# USB.net
KiCad netlist of a schematic drawn in Altium Designer
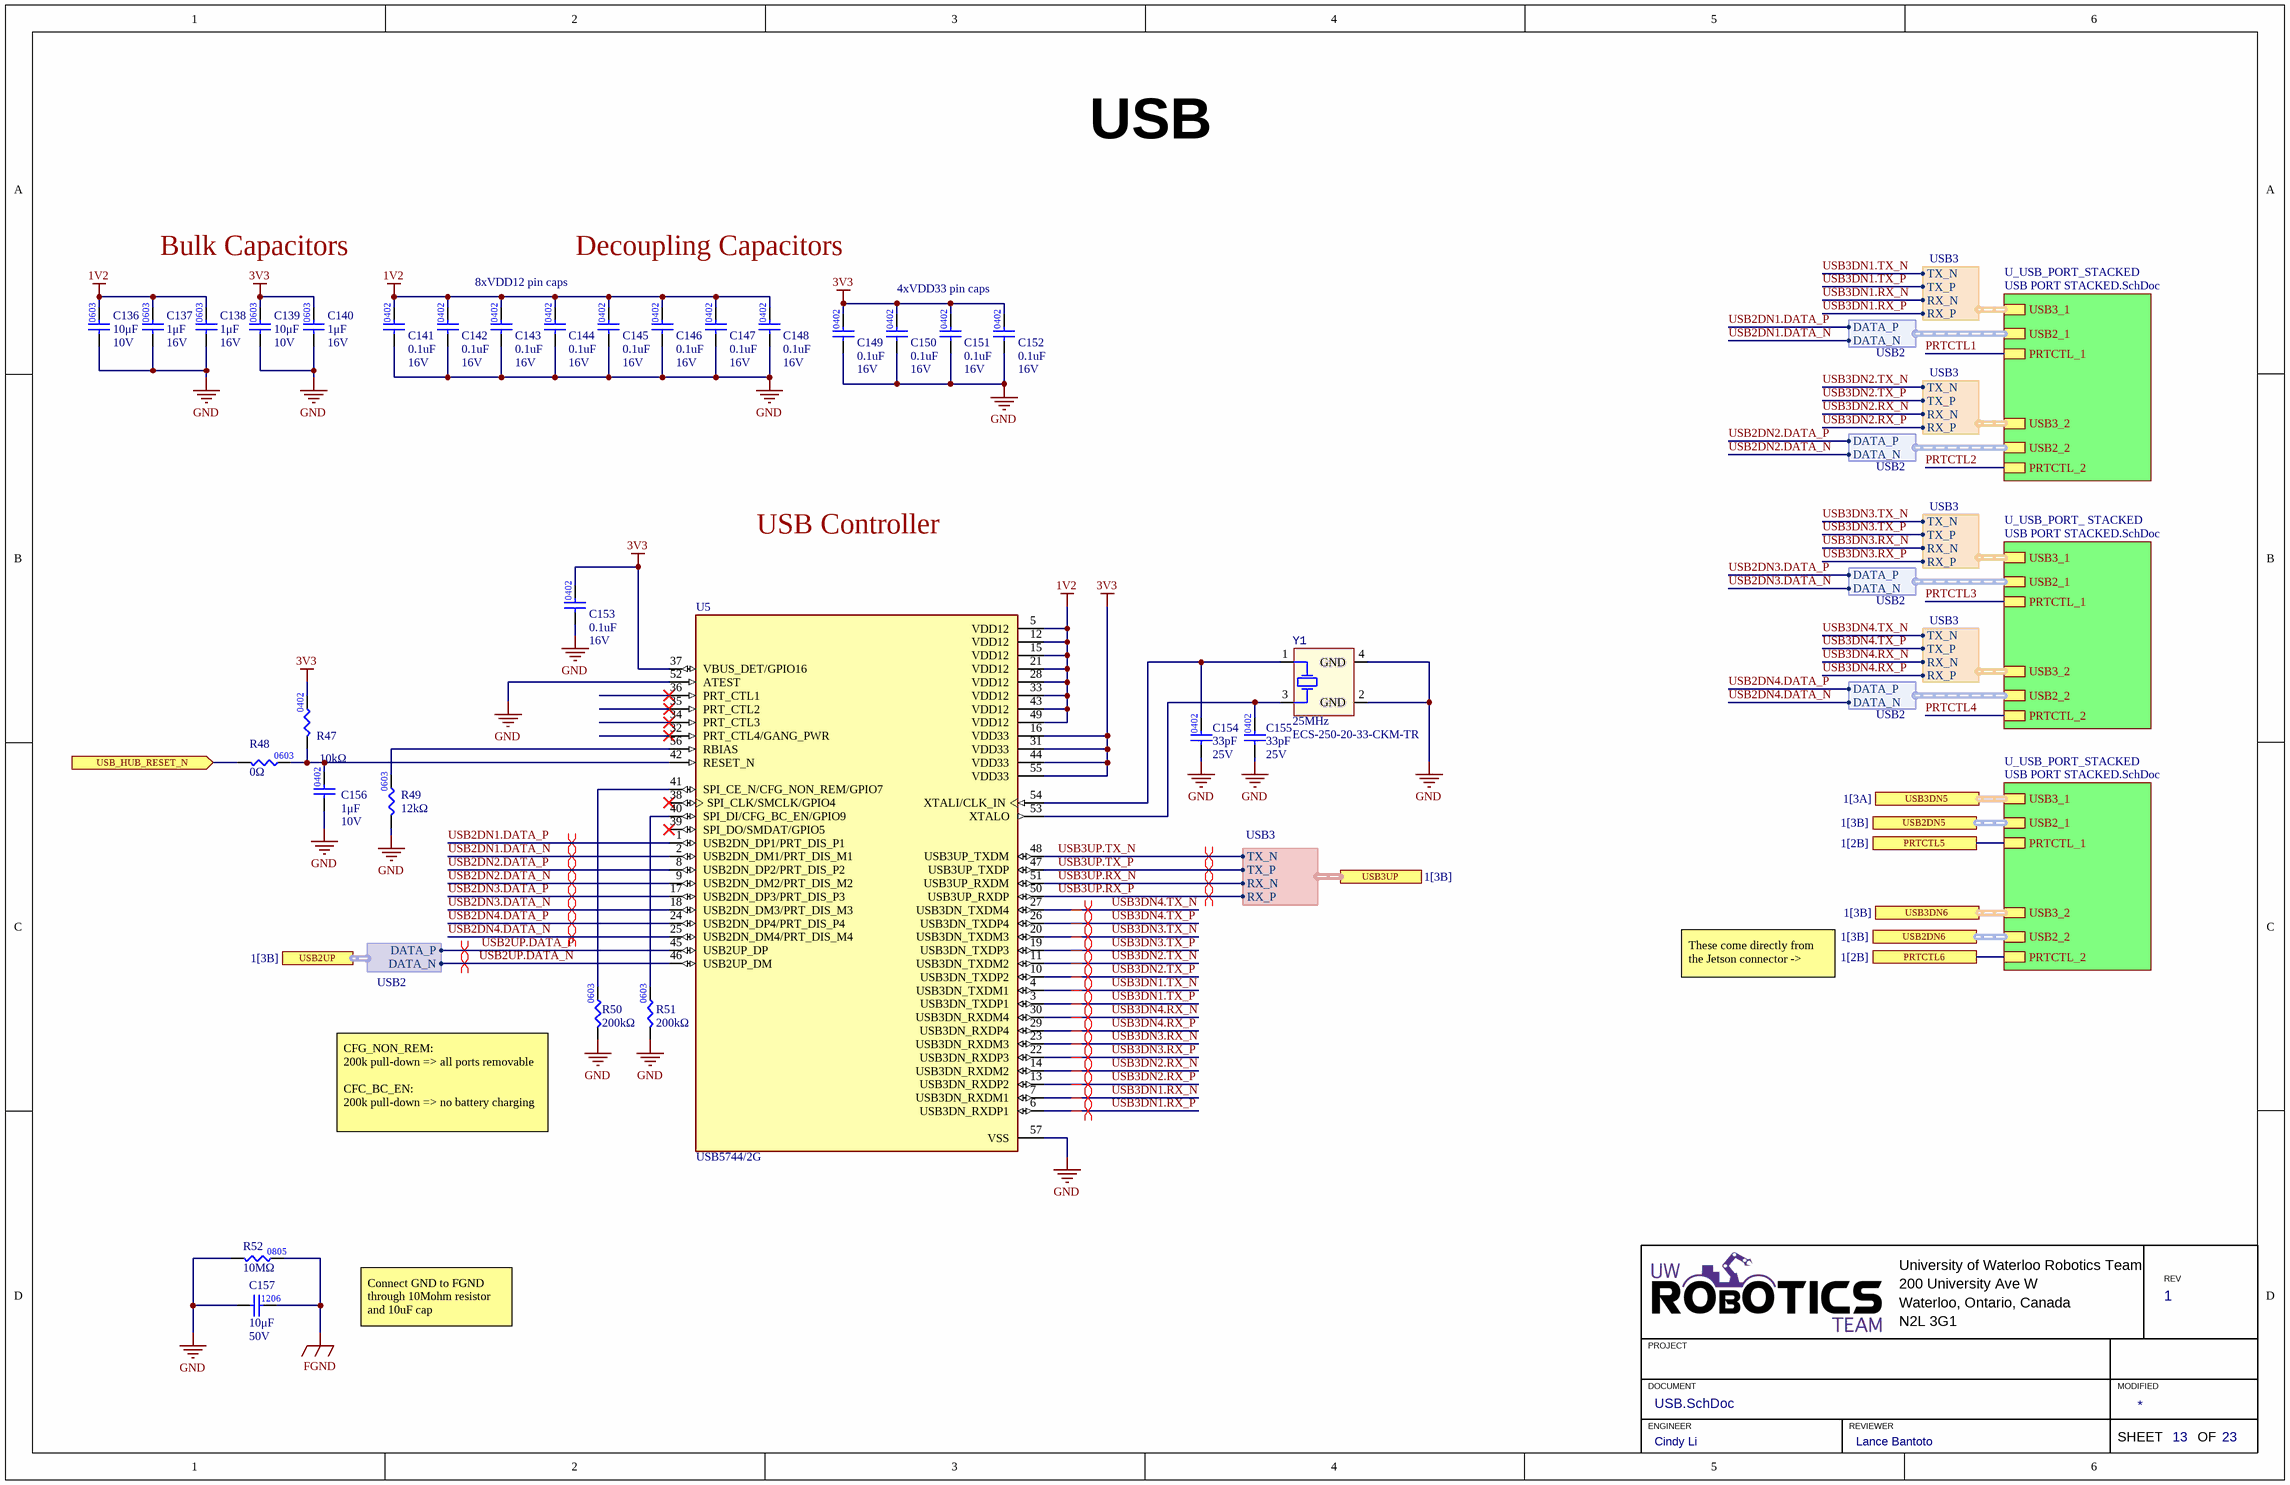
[diagram p0: USB.SchDoc]

(export (version "E")
  (design (tool "Eeschema 10.0.6"))
  (components
    (comp (ref "C136")
      (value "10μF")
      (footprint "CAP0603")
      (description "CAP CER 10UF 10V X5R 0603")
      (fields (field (name "VOLTAGE RATING") "10V") (field (name "Comment") "CAP_10uF_10V_0603"))
      (libsource (lib "UWRT_Schematic_Library_2020") (part "CAP_10uF_10V_0603"))
    )
    (comp (ref "C137")
      (value "1μF")
      (footprint "CAP0603")
      (description "CAP CER 1UF 16V Y5V 0603")
      (fields (field (name "VOLTAGE RATING") "16V") (field (name "Comment") "CAP_1uF_16V_0603"))
      (libsource (lib "UWRT_Schematic_Library_2020") (part "CAP_1uF_16V_0603"))
    )
    (comp (ref "C138")
      (value "1μF")
      (footprint "CAP0603")
      (description "CAP CER 1UF 16V Y5V 0603")
      (fields (field (name "VOLTAGE RATING") "16V") (field (name "Comment") "CAP_1uF_16V_0603"))
      (libsource (lib "UWRT_Schematic_Library_2020") (part "CAP_1uF_16V_0603"))
    )
    (comp (ref "C139")
      (value "10μF")
      (footprint "CAP0603")
      (description "CAP CER 10UF 10V X5R 0603")
      (fields (field (name "VOLTAGE RATING") "10V") (field (name "Comment") "CAP_10uF_10V_0603"))
      (libsource (lib "UWRT_Schematic_Library_2020") (part "CAP_10uF_10V_0603"))
    )
    (comp (ref "C140")
      (value "1μF")
      (footprint "CAP0603")
      (description "CAP CER 1UF 16V Y5V 0603")
      (fields (field (name "VOLTAGE RATING") "16V") (field (name "Comment") "CAP_1uF_16V_0603"))
      (libsource (lib "UWRT_Schematic_Library_2020") (part "CAP_1uF_16V_0603"))
    )
    (comp (ref "C141")
      (value "CAP_0.1uF_16V_X7R_0402")
      (footprint "CAP0402")
      (description "Ceramic Capacitor, Ceramic")
      (fields
        (field (name "MANUFACTURER") "Taiyo Yuden")
        (field (name "MANUFACTURER PART NUMBER") "LMK212AC6106MD-T")
        (field (name "RATED DC VOLTAGE (URDC)") "16V")
        (field (name "CAPACITANCE") "0.1uF")
      )
      (libsource (lib "UWRT_Schematic_Library_2020") (part "CAP_0.1uF_16V_X7R_0402"))
    )
    (comp (ref "C142")
      (value "CAP_0.1uF_16V_X7R_0402")
      (footprint "CAP0402")
      (description "Ceramic Capacitor, Ceramic")
      (fields
        (field (name "MANUFACTURER") "Taiyo Yuden")
        (field (name "MANUFACTURER PART NUMBER") "LMK212AC6106MD-T")
        (field (name "RATED DC VOLTAGE (URDC)") "16V")
        (field (name "CAPACITANCE") "0.1uF")
      )
      (libsource (lib "UWRT_Schematic_Library_2020") (part "CAP_0.1uF_16V_X7R_0402"))
    )
    (comp (ref "C143")
      (value "CAP_0.1uF_16V_X7R_0402")
      (footprint "CAP0402")
      (description "Ceramic Capacitor, Ceramic")
      (fields
        (field (name "MANUFACTURER") "Taiyo Yuden")
        (field (name "MANUFACTURER PART NUMBER") "LMK212AC6106MD-T")
        (field (name "RATED DC VOLTAGE (URDC)") "16V")
        (field (name "CAPACITANCE") "0.1uF")
      )
      (libsource (lib "UWRT_Schematic_Library_2020") (part "CAP_0.1uF_16V_X7R_0402"))
    )
    (comp (ref "C144")
      (value "CAP_0.1uF_16V_X7R_0402")
      (footprint "CAP0402")
      (description "Ceramic Capacitor, Ceramic")
      (fields
        (field (name "MANUFACTURER") "Taiyo Yuden")
        (field (name "MANUFACTURER PART NUMBER") "LMK212AC6106MD-T")
        (field (name "RATED DC VOLTAGE (URDC)") "16V")
        (field (name "CAPACITANCE") "0.1uF")
      )
      (libsource (lib "UWRT_Schematic_Library_2020") (part "CAP_0.1uF_16V_X7R_0402"))
    )
    (comp (ref "C145")
      (value "CAP_0.1uF_16V_X7R_0402")
      (footprint "CAP0402")
      (description "Ceramic Capacitor, Ceramic")
      (fields
        (field (name "MANUFACTURER") "Taiyo Yuden")
        (field (name "MANUFACTURER PART NUMBER") "LMK212AC6106MD-T")
        (field (name "RATED DC VOLTAGE (URDC)") "16V")
        (field (name "CAPACITANCE") "0.1uF")
      )
      (libsource (lib "UWRT_Schematic_Library_2020") (part "CAP_0.1uF_16V_X7R_0402"))
    )
    (comp (ref "C146")
      (value "CAP_0.1uF_16V_X7R_0402")
      (footprint "CAP0402")
      (description "Ceramic Capacitor, Ceramic")
      (fields
        (field (name "MANUFACTURER") "Taiyo Yuden")
        (field (name "MANUFACTURER PART NUMBER") "LMK212AC6106MD-T")
        (field (name "RATED DC VOLTAGE (URDC)") "16V")
        (field (name "CAPACITANCE") "0.1uF")
      )
      (libsource (lib "UWRT_Schematic_Library_2020") (part "CAP_0.1uF_16V_X7R_0402"))
    )
    (comp (ref "C147")
      (value "CAP_0.1uF_16V_X7R_0402")
      (footprint "CAP0402")
      (description "Ceramic Capacitor, Ceramic")
      (fields
        (field (name "MANUFACTURER") "Taiyo Yuden")
        (field (name "MANUFACTURER PART NUMBER") "LMK212AC6106MD-T")
        (field (name "RATED DC VOLTAGE (URDC)") "16V")
        (field (name "CAPACITANCE") "0.1uF")
      )
      (libsource (lib "UWRT_Schematic_Library_2020") (part "CAP_0.1uF_16V_X7R_0402"))
    )
    (comp (ref "C148")
      (value "CAP_0.1uF_16V_X7R_0402")
      (footprint "CAP0402")
      (description "Ceramic Capacitor, Ceramic")
      (fields
        (field (name "MANUFACTURER") "Taiyo Yuden")
        (field (name "MANUFACTURER PART NUMBER") "LMK212AC6106MD-T")
        (field (name "RATED DC VOLTAGE (URDC)") "16V")
        (field (name "CAPACITANCE") "0.1uF")
      )
      (libsource (lib "UWRT_Schematic_Library_2020") (part "CAP_0.1uF_16V_X7R_0402"))
    )
    (comp (ref "C149")
      (value "CAP_0.1uF_16V_X7R_0402")
      (footprint "CAP0402")
      (description "Ceramic Capacitor, Ceramic")
      (fields
        (field (name "MANUFACTURER") "Taiyo Yuden")
        (field (name "MANUFACTURER PART NUMBER") "LMK212AC6106MD-T")
        (field (name "RATED DC VOLTAGE (URDC)") "16V")
        (field (name "CAPACITANCE") "0.1uF")
      )
      (libsource (lib "UWRT_Schematic_Library_2020") (part "CAP_0.1uF_16V_X7R_0402"))
    )
    (comp (ref "C150")
      (value "CAP_0.1uF_16V_X7R_0402")
      (footprint "CAP0402")
      (description "Ceramic Capacitor, Ceramic")
      (fields
        (field (name "MANUFACTURER") "Taiyo Yuden")
        (field (name "MANUFACTURER PART NUMBER") "LMK212AC6106MD-T")
        (field (name "RATED DC VOLTAGE (URDC)") "16V")
        (field (name "CAPACITANCE") "0.1uF")
      )
      (libsource (lib "UWRT_Schematic_Library_2020") (part "CAP_0.1uF_16V_X7R_0402"))
    )
    (comp (ref "C151")
      (value "CAP_0.1uF_16V_X7R_0402")
      (footprint "CAP0402")
      (description "Ceramic Capacitor, Ceramic")
      (fields
        (field (name "MANUFACTURER") "Taiyo Yuden")
        (field (name "MANUFACTURER PART NUMBER") "LMK212AC6106MD-T")
        (field (name "RATED DC VOLTAGE (URDC)") "16V")
        (field (name "CAPACITANCE") "0.1uF")
      )
      (libsource (lib "UWRT_Schematic_Library_2020") (part "CAP_0.1uF_16V_X7R_0402"))
    )
    (comp (ref "C152")
      (value "CAP_0.1uF_16V_X7R_0402")
      (footprint "CAP0402")
      (description "Ceramic Capacitor, Ceramic")
      (fields
        (field (name "MANUFACTURER") "Taiyo Yuden")
        (field (name "MANUFACTURER PART NUMBER") "LMK212AC6106MD-T")
        (field (name "RATED DC VOLTAGE (URDC)") "16V")
        (field (name "CAPACITANCE") "0.1uF")
      )
      (libsource (lib "UWRT_Schematic_Library_2020") (part "CAP_0.1uF_16V_X7R_0402"))
    )
    (comp (ref "C153")
      (value "CAP_0.1uF_16V_X7R_0402")
      (footprint "CAP0402")
      (description "Ceramic Capacitor, Ceramic")
      (fields
        (field (name "MANUFACTURER") "Taiyo Yuden")
        (field (name "MANUFACTURER PART NUMBER") "LMK212AC6106MD-T")
        (field (name "RATED DC VOLTAGE (URDC)") "16V")
        (field (name "CAPACITANCE") "0.1uF")
      )
      (libsource (lib "UWRT_Schematic_Library_2020") (part "CAP_0.1uF_16V_X7R_0402"))
    )
    (comp (ref "C154")
      (value "33pF")
      (footprint "CAP0402")
      (description "CAP CER 33PF 25V C0G/NP0 0402")
      (fields (field (name "VOLTAGE RATING") "25V") (field (name "Comment") "CAP_33pF_25V_0402"))
      (libsource (lib "UWRT_Schematic_Library_2020") (part "CAP_33pF_25V_0402"))
    )
    (comp (ref "C155")
      (value "33pF")
      (footprint "CAP0402")
      (description "CAP CER 33PF 25V C0G/NP0 0402")
      (fields (field (name "VOLTAGE RATING") "25V") (field (name "Comment") "CAP_33pF_25V_0402"))
      (libsource (lib "UWRT_Schematic_Library_2020") (part "CAP_33pF_25V_0402"))
    )
    (comp (ref "C156")
      (value "CAP_1UF_10V_0402_X5R")
      (footprint "CAP0402")
      (description "CAP CER 1UF 10V X5R 0402")
      (fields
        (field (name "MANUFACTURER") "Kyocera AVX")
        (field (name "MANUFACTURER PART NUMBER") "0402ZD105MAT2A")
        (field (name "CAPACITANCE") "1μF")
        (field (name "RATED DC VOLTAGE (URDC)") "10V")
      )
      (libsource (lib "UWRT_Schematic_Library_2020") (part "CAP_1UF_10V_0402_X5R"))
    )
    (comp (ref "C157")
      (value "10μF")
      (footprint "CAP1206")
      (description "CAP CER 10UF 50V X5R 1206")
      (fields (field (name "VOLTAGE RATING") "50V") (field (name "Comment") "CAP_10uF_50V_1206"))
      (libsource (lib "UWRT_Schematic_Library_2020") (part "CAP_10uF_50V_1206"))
    )
    (comp (ref "R47")
      (value "RES_10kΩ_0402_1%")
      (footprint "RES0402")
      (description "RES 10K OHM 1% 1/16W 0402")
      (fields (field (name "TOLERANCE") "1%") (field (name "RESISTANCE") "10kΩ"))
      (libsource (lib "UWRT_Schematic_Library_2020") (part "RES_10kΩ_0402_1%"))
    )
    (comp (ref "R48")
      (value "0Ω")
      (footprint "RES0603")
      (description "RES 0 OHM JUMPER 1/10W 0603")
      (fields (field (name "Comment") "RES_0Ω_0603"))
      (libsource (lib "UWRT_Schematic_Library_2020") (part "RES_0Ω_0603"))
    )
    (comp (ref "R49")
      (value "12kΩ")
      (footprint "RES0603")
      (description "RES 12K OHM 1% 1/10W 0603")
      (fields (field (name "POWER") "0.1W") (field (name "TOLERANCE") "1%"))
      (libsource (lib "UWRT_Schematic_Library_2020") (part "RES_12kΩ_0603_1%"))
    )
    (comp (ref "R50")
      (value "200kΩ")
      (footprint "RES0603")
      (description "RES SMD 200K OHM 5% 1/10W 0603")
      (fields (field (name "Comment") "RES_200kΩ_0603_5%"))
      (libsource (lib "UWRT_Schematic_Library_2020") (part "RES_200kΩ_0603_5%"))
    )
    (comp (ref "R51")
      (value "200kΩ")
      (footprint "RES0603")
      (description "RES SMD 200K OHM 5% 1/10W 0603")
      (fields (field (name "Comment") "RES_200kΩ_0603_5%"))
      (libsource (lib "UWRT_Schematic_Library_2020") (part "RES_200kΩ_0603_5%"))
    )
    (comp (ref "R52")
      (value "10MΩ")
      (footprint "RES0805")
      (description "RES 10M OHM 5% 1/8W 0805")
      (fields (field (name "Comment") "RES_10MΩ_0805"))
      (libsource (lib "UWRT_Schematic_Library_2020") (part "RES_10MΩ_0805_5%"))
    )
    (comp (ref "U5")
      (value "USB5744/2G")
      (footprint "QFN40P700X700X100-57N")
      (description "USB Hub Controller USB 3.1 USB Interface 56-VQFN (7x7)")
      (libsource (lib "UWRT_Schematic_Library_2020") (part "USB5744/2G"))
    )
    (comp (ref "Y1")
      (value "CRYSTAL_25MHZ_20PF")
      (footprint "XTAL_ECS-250-20-33-CKM-TR")
      (description "CRYSTAL 25.0000MHZ 20PF SMD")
      (fields
        (field (name "FREQUENCY") "25MHz")
        (field (name "MANUFACTURER PART NUMBER 1") "ECS-250-20-33-CKM-TR")
      )
      (libsource (lib "UWRT_Schematic_Library_2020") (part "CRYSTAL_25MHZ_20PF"))
    )
  )
  (nets
    (net (code "9") (name "/USB2DN1.DATA_N") (class "Default")
      (node (ref "U5") (pin "2") (pinfunction "USB2DN_DM1/PRT_DIS_M1_2") (pintype "bidirectional"))
    )
    (net (code "10") (name "/USB2DN1.DATA_P") (class "Default")
      (node (ref "U5") (pin "1") (pinfunction "USB2DN_DP1/PRT_DIS_P1_1") (pintype "bidirectional"))
    )
    (net (code "11") (name "/USB2DN2.DATA_N") (class "Default")
      (node (ref "U5") (pin "9") (pinfunction "USB2DN_DM2/PRT_DIS_M2_9") (pintype "bidirectional"))
    )
    (net (code "12") (name "/USB2DN2.DATA_P") (class "Default")
      (node (ref "U5") (pin "8") (pinfunction "USB2DN_DP2/PRT_DIS_P2_8") (pintype "bidirectional"))
    )
    (net (code "13") (name "/USB2DN3.DATA_N") (class "Default")
      (node (ref "U5") (pin "18") (pinfunction "USB2DN_DM3/PRT_DIS_M3_18") (pintype "bidirectional"))
    )
    (net (code "14") (name "/USB2DN3.DATA_P") (class "Default")
      (node (ref "U5") (pin "17") (pinfunction "USB2DN_DP3/PRT_DIS_P3_17") (pintype "bidirectional"))
    )
    (net (code "15") (name "/USB2DN4.DATA_N") (class "Default")
      (node (ref "U5") (pin "25") (pinfunction "USB2DN_DM4/PRT_DIS_M4_25") (pintype "bidirectional"))
    )
    (net (code "16") (name "/USB2DN4.DATA_P") (class "Default")
      (node (ref "U5") (pin "24") (pinfunction "USB2DN_DP4/PRT_DIS_P4_24") (pintype "bidirectional"))
    )
    (net (code "19") (name "/USB2UP.DATA_N") (class "Default")
      (node (ref "U5") (pin "46") (pinfunction "USB2UP_DM_46") (pintype "bidirectional"))
    )
    (net (code "20") (name "/USB2UP.DATA_P") (class "Default")
      (node (ref "U5") (pin "45") (pinfunction "USB2UP_DP_45") (pintype "bidirectional"))
    )
    (net (code "21") (name "/USB3DN1.RX_N") (class "Default")
      (node (ref "U5") (pin "7") (pinfunction "USB3DN_RXDM1_7") (pintype "bidirectional"))
    )
    (net (code "22") (name "/USB3DN1.RX_P") (class "Default")
      (node (ref "U5") (pin "6") (pinfunction "USB3DN_RXDP1_6") (pintype "bidirectional"))
    )
    (net (code "23") (name "/USB3DN1.TX_N") (class "Default")
      (node (ref "U5") (pin "4") (pinfunction "USB3DN_TXDM1_4") (pintype "bidirectional"))
    )
    (net (code "24") (name "/USB3DN1.TX_P") (class "Default")
      (node (ref "U5") (pin "3") (pinfunction "USB3DN_TXDP1_3") (pintype "bidirectional"))
    )
    (net (code "25") (name "/USB3DN2.RX_N") (class "Default")
      (node (ref "U5") (pin "14") (pinfunction "USB3DN_RXDM2_14") (pintype "bidirectional"))
    )
    (net (code "26") (name "/USB3DN2.RX_P") (class "Default")
      (node (ref "U5") (pin "13") (pinfunction "USB3DN_RXDP2_13") (pintype "bidirectional"))
    )
    (net (code "27") (name "/USB3DN2.TX_N") (class "Default")
      (node (ref "U5") (pin "11") (pinfunction "USB3DN_TXDM2_11") (pintype "bidirectional"))
    )
    (net (code "28") (name "/USB3DN2.TX_P") (class "Default")
      (node (ref "U5") (pin "10") (pinfunction "USB3DN_TXDP2_10") (pintype "bidirectional"))
    )
    (net (code "29") (name "/USB3DN3.RX_N") (class "Default")
      (node (ref "U5") (pin "23") (pinfunction "USB3DN_RXDM3_23") (pintype "bidirectional"))
    )
    (net (code "30") (name "/USB3DN3.RX_P") (class "Default")
      (node (ref "U5") (pin "22") (pinfunction "USB3DN_RXDP3_22") (pintype "bidirectional"))
    )
    (net (code "31") (name "/USB3DN3.TX_N") (class "Default")
      (node (ref "U5") (pin "20") (pinfunction "USB3DN_TXDM3_20") (pintype "bidirectional"))
    )
    (net (code "32") (name "/USB3DN3.TX_P") (class "Default")
      (node (ref "U5") (pin "19") (pinfunction "USB3DN_TXDP3_19") (pintype "bidirectional"))
    )
    (net (code "33") (name "/USB3DN4.RX_N") (class "Default")
      (node (ref "U5") (pin "30") (pinfunction "USB3DN_RXDM4_30") (pintype "bidirectional"))
    )
    (net (code "34") (name "/USB3DN4.RX_P") (class "Default")
      (node (ref "U5") (pin "29") (pinfunction "USB3DN_RXDP4_29") (pintype "bidirectional"))
    )
    (net (code "35") (name "/USB3DN4.TX_N") (class "Default")
      (node (ref "U5") (pin "27") (pinfunction "USB3DN_TXDM4_27") (pintype "bidirectional"))
    )
    (net (code "36") (name "/USB3DN4.TX_P") (class "Default")
      (node (ref "U5") (pin "26") (pinfunction "USB3DN_TXDP4_26") (pintype "bidirectional"))
    )
    (net (code "39") (name "/USB3UP.RX_N") (class "Default")
      (node (ref "U5") (pin "51") (pinfunction "USB3UP_RXDM_51") (pintype "bidirectional"))
    )
    (net (code "40") (name "/USB3UP.RX_P") (class "Default")
      (node (ref "U5") (pin "50") (pinfunction "USB3UP_RXDP_50") (pintype "bidirectional"))
    )
    (net (code "41") (name "/USB3UP.TX_N") (class "Default")
      (node (ref "U5") (pin "48") (pinfunction "USB3UP_TXDM_48") (pintype "bidirectional"))
    )
    (net (code "42") (name "/USB3UP.TX_P") (class "Default")
      (node (ref "U5") (pin "47") (pinfunction "USB3UP_TXDP_47") (pintype "bidirectional"))
    )
    (net (code "43") (name "/USB_HUB_RESET_N") (class "Default")
      (node (ref "R48") (pin "1") (pinfunction "1_1") (pintype "passive"))
    )
    (net (code "46") (name "1V2") (class "Default")
      (node (ref "C136") (pin "2") (pinfunction "2_2") (pintype "passive"))
      (node (ref "C137") (pin "2") (pinfunction "2_2") (pintype "passive"))
      (node (ref "C138") (pin "2") (pinfunction "2_2") (pintype "passive"))
      (node (ref "C141") (pin "2") (pinfunction "2_2") (pintype "passive"))
      (node (ref "C142") (pin "2") (pinfunction "2_2") (pintype "passive"))
      (node (ref "C143") (pin "2") (pinfunction "2_2") (pintype "passive"))
      (node (ref "C144") (pin "2") (pinfunction "2_2") (pintype "passive"))
      (node (ref "C145") (pin "2") (pinfunction "2_2") (pintype "passive"))
      (node (ref "C146") (pin "2") (pinfunction "2_2") (pintype "passive"))
      (node (ref "C147") (pin "2") (pinfunction "2_2") (pintype "passive"))
      (node (ref "C148") (pin "2") (pinfunction "2_2") (pintype "passive"))
      (node (ref "U5") (pin "12") (pinfunction "VDD12_12") (pintype "power_in"))
      (node (ref "U5") (pin "15") (pinfunction "VDD12_15") (pintype "power_in"))
      (node (ref "U5") (pin "21") (pinfunction "VDD12_21") (pintype "power_in"))
      (node (ref "U5") (pin "28") (pinfunction "VDD12_28") (pintype "power_in"))
      (node (ref "U5") (pin "33") (pinfunction "VDD12_33") (pintype "power_in"))
      (node (ref "U5") (pin "43") (pinfunction "VDD12_43") (pintype "power_in"))
      (node (ref "U5") (pin "49") (pinfunction "VDD12_49") (pintype "power_in"))
      (node (ref "U5") (pin "5") (pinfunction "VDD12_5") (pintype "power_in"))
    )
    (net (code "47") (name "3V3") (class "Default")
      (node (ref "C139") (pin "2") (pinfunction "2_2") (pintype "passive"))
      (node (ref "C140") (pin "2") (pinfunction "2_2") (pintype "passive"))
      (node (ref "C149") (pin "2") (pinfunction "2_2") (pintype "passive"))
      (node (ref "C150") (pin "2") (pinfunction "2_2") (pintype "passive"))
      (node (ref "C151") (pin "2") (pinfunction "2_2") (pintype "passive"))
      (node (ref "C152") (pin "2") (pinfunction "2_2") (pintype "passive"))
      (node (ref "C153") (pin "2") (pinfunction "2_2") (pintype "passive"))
      (node (ref "R47") (pin "2") (pinfunction "2_2") (pintype "passive"))
      (node (ref "U5") (pin "16") (pinfunction "VDD33_16") (pintype "power_in"))
      (node (ref "U5") (pin "31") (pinfunction "VDD33_31") (pintype "power_in"))
      (node (ref "U5") (pin "37") (pinfunction "VBUS_DET/GPIO16_37") (pintype "bidirectional"))
      (node (ref "U5") (pin "44") (pinfunction "VDD33_44") (pintype "power_in"))
      (node (ref "U5") (pin "55") (pinfunction "VDD33_55") (pintype "power_in"))
    )
    (net (code "48") (name "FGND") (class "Default")
      (node (ref "C157") (pin "2") (pinfunction "2_2") (pintype "passive"))
      (node (ref "R52") (pin "2") (pinfunction "2_2") (pintype "passive"))
    )
    (net (code "49") (name "GND") (class "Default")
      (node (ref "C136") (pin "1") (pinfunction "1_1") (pintype "passive"))
      (node (ref "C137") (pin "1") (pinfunction "1_1") (pintype "passive"))
      (node (ref "C138") (pin "1") (pinfunction "1_1") (pintype "passive"))
      (node (ref "C139") (pin "1") (pinfunction "1_1") (pintype "passive"))
      (node (ref "C140") (pin "1") (pinfunction "1_1") (pintype "passive"))
      (node (ref "C141") (pin "1") (pinfunction "1_1") (pintype "passive"))
      (node (ref "C142") (pin "1") (pinfunction "1_1") (pintype "passive"))
      (node (ref "C143") (pin "1") (pinfunction "1_1") (pintype "passive"))
      (node (ref "C144") (pin "1") (pinfunction "1_1") (pintype "passive"))
      (node (ref "C145") (pin "1") (pinfunction "1_1") (pintype "passive"))
      (node (ref "C146") (pin "1") (pinfunction "1_1") (pintype "passive"))
      (node (ref "C147") (pin "1") (pinfunction "1_1") (pintype "passive"))
      (node (ref "C148") (pin "1") (pinfunction "1_1") (pintype "passive"))
      (node (ref "C149") (pin "1") (pinfunction "1_1") (pintype "passive"))
      (node (ref "C150") (pin "1") (pinfunction "1_1") (pintype "passive"))
      (node (ref "C151") (pin "1") (pinfunction "1_1") (pintype "passive"))
      (node (ref "C152") (pin "1") (pinfunction "1_1") (pintype "passive"))
      (node (ref "C153") (pin "1") (pinfunction "1_1") (pintype "passive"))
      (node (ref "C154") (pin "1") (pinfunction "1_1") (pintype "passive"))
      (node (ref "C155") (pin "1") (pinfunction "1_1") (pintype "passive"))
      (node (ref "C156") (pin "1") (pinfunction "1_1") (pintype "passive"))
      (node (ref "C157") (pin "1") (pinfunction "1_1") (pintype "passive"))
      (node (ref "R49") (pin "1") (pinfunction "1_1") (pintype "passive"))
      (node (ref "R50") (pin "1") (pinfunction "1_1") (pintype "passive"))
      (node (ref "R51") (pin "1") (pinfunction "1_1") (pintype "passive"))
      (node (ref "R52") (pin "1") (pinfunction "1_1") (pintype "passive"))
      (node (ref "U5") (pin "52") (pinfunction "ATEST_52") (pintype "input"))
      (node (ref "U5") (pin "57") (pinfunction "VSS_57") (pintype "power_in"))
      (node (ref "Y1") (pin "2") (pinfunction "GND_2") (pintype "power_in"))
      (node (ref "Y1") (pin "4") (pinfunction "GND_4") (pintype "passive"))
    )
    (net (code "50") (name "Net-(U5-RBIAS)") (class "Default")
      (node (ref "R49") (pin "2") (pinfunction "2_2") (pintype "passive"))
      (node (ref "U5") (pin "56") (pinfunction "RBIAS_56") (pintype "input"))
    )
    (net (code "51") (name "Net-(U5-RESET_N)") (class "Default")
      (node (ref "C156") (pin "2") (pinfunction "2_2") (pintype "passive"))
      (node (ref "R47") (pin "1") (pinfunction "1_1") (pintype "passive"))
      (node (ref "R48") (pin "2") (pinfunction "2_2") (pintype "passive"))
      (node (ref "U5") (pin "42") (pinfunction "RESET_N_42") (pintype "input"))
    )
    (net (code "52") (name "Net-(U5-SPI_CE_N{slash}CFG_NON_REM{slash}GPIO7)") (class "Default")
      (node (ref "R50") (pin "2") (pinfunction "2_2") (pintype "passive"))
      (node (ref "U5") (pin "41") (pinfunction "SPI_CE_N/CFG_NON_REM/GPIO7_41") (pintype "bidirectional"))
    )
    (net (code "53") (name "Net-(U5-SPI_DI{slash}CFG_BC_EN{slash}GPIO9)") (class "Default")
      (node (ref "R51") (pin "2") (pinfunction "2_2") (pintype "passive"))
      (node (ref "U5") (pin "40") (pinfunction "SPI_DI/CFG_BC_EN/GPIO9_40") (pintype "bidirectional"))
    )
    (net (code "54") (name "Net-(U5-XTALI{slash}CLK_IN)") (class "Default")
      (node (ref "C154") (pin "2") (pinfunction "2_2") (pintype "passive"))
      (node (ref "U5") (pin "54") (pinfunction "XTALI/CLK_IN_54") (pintype "input"))
      (node (ref "Y1") (pin "1") (pinfunction "HOT_1") (pintype "passive"))
    )
    (net (code "55") (name "Net-(U5-XTALO)") (class "Default")
      (node (ref "C155") (pin "2") (pinfunction "2_2") (pintype "passive"))
      (node (ref "U5") (pin "53") (pinfunction "XTALO_53") (pintype "output"))
      (node (ref "Y1") (pin "3") (pinfunction "HOT_3") (pintype "passive"))
    )
    (net (code "56") (name "unconnected-(U5-PRT_CTL1-Pad36)") (class "Default")
      (node (ref "U5") (pin "36") (pinfunction "PRT_CTL1_36") (pintype "input+no_connect"))
    )
    (net (code "57") (name "unconnected-(U5-PRT_CTL2-Pad35)") (class "Default")
      (node (ref "U5") (pin "35") (pinfunction "PRT_CTL2_35") (pintype "input+no_connect"))
    )
    (net (code "58") (name "unconnected-(U5-PRT_CTL3-Pad34)") (class "Default")
      (node (ref "U5") (pin "34") (pinfunction "PRT_CTL3_34") (pintype "input+no_connect"))
    )
    (net (code "59") (name "unconnected-(U5-PRT_CTL4{slash}GANG_PWR-Pad32)") (class "Default")
      (node (ref "U5") (pin "32") (pinfunction "PRT_CTL4/GANG_PWR_32") (pintype "input+no_connect"))
    )
    (net (code "60") (name "unconnected-(U5-SPI_CLK{slash}SMCLK{slash}GPIO4-Pad38)") (class "Default")
      (node (ref "U5") (pin "38") (pinfunction "SPI_CLK/SMCLK/GPIO4_38") (pintype "bidirectional+no_connect"))
    )
    (net (code "61") (name "unconnected-(U5-SPI_DO{slash}SMDAT{slash}GPIO5-Pad39)") (class "Default")
      (node (ref "U5") (pin "39") (pinfunction "SPI_DO/SMDAT/GPIO5_39") (pintype "bidirectional+no_connect"))
    )
  )
)
